# SensWear_Debug_UART2USB_1.net
KiCad netlist of a schematic drawn in Altium Designer
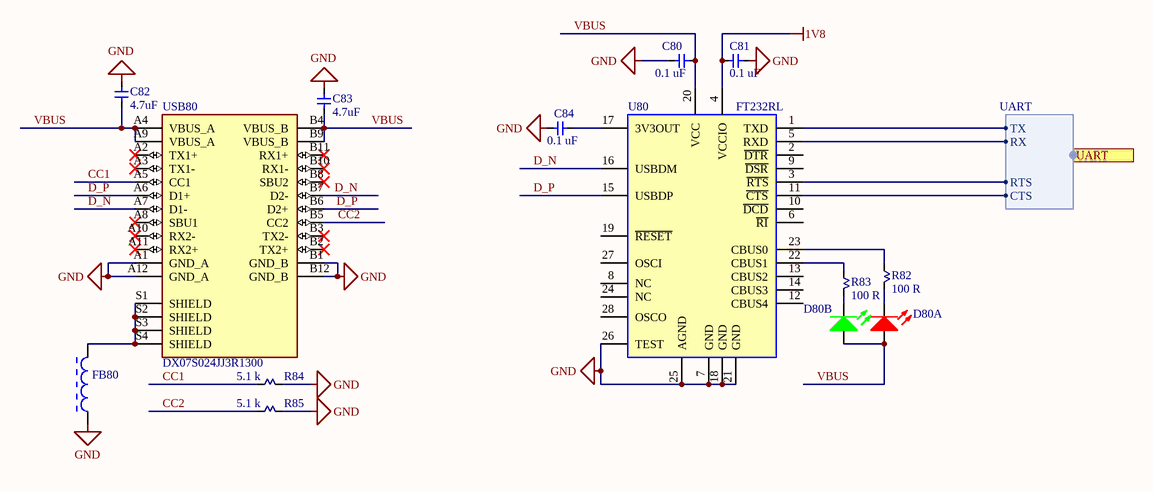
[diagram p0: SensWear_Debug_UART2USB_1.SchDoc]

(export (version "E")
  (design (tool "Eeschema 10.0.6"))
  (components
    (comp (ref "C80")
      (value "0.1 uF")
      (footprint "CAPC1005X05N")
      (description "CAP CER 0.1UF 16V X5R 0402")
      (fields
        (field (name "MANUFACTURER") "Murata Electronics")
        (field (name "MANUFACTURER PART NUMBER") "GRM155R61C104KA88D")
      )
      (libsource (lib "PingbitComponents") (part "GRM155R61C104KA88D"))
    )
    (comp (ref "C81")
      (value "0.1 uF")
      (footprint "CAPC1005X05N")
      (description "CAP CER 0.1UF 16V X5R 0402")
      (fields
        (field (name "MANUFACTURER") "Murata Electronics")
        (field (name "MANUFACTURER PART NUMBER") "GRM155R61C104KA88D")
      )
      (libsource (lib "PingbitComponents") (part "GRM155R61C104KA88D"))
    )
    (comp (ref "C82")
      (value "4.7uF")
      (footprint "CAPC1610X05N")
      (description "Cap Ceramic 4.7uF 10V X5R 10% Pad SMD 0603 85C T/R")
      (fields
        (field (name "MANUFACTURER") "Samsung")
        (field (name "MANUFACTURER PART NUMBER") "CL10A475KP8NNNC")
      )
      (libsource (lib "PingBitComponents") (part "CL10A475KP8NNNC"))
    )
    (comp (ref "C83")
      (value "4.7uF")
      (footprint "CAPC1610X05N")
      (description "Cap Ceramic 4.7uF 10V X5R 10% Pad SMD 0603 85C T/R")
      (fields
        (field (name "MANUFACTURER") "Samsung")
        (field (name "MANUFACTURER PART NUMBER") "CL10A475KP8NNNC")
      )
      (libsource (lib "PingBitComponents") (part "CL10A475KP8NNNC"))
    )
    (comp (ref "C84")
      (value "0.1 uF")
      (footprint "CAPC1005X05N")
      (description "CAP CER 0.1UF 16V X5R 0402")
      (fields
        (field (name "MANUFACTURER") "Murata Electronics")
        (field (name "MANUFACTURER PART NUMBER") "GRM155R61C104KA88D")
      )
      (libsource (lib "PingbitComponents") (part "GRM155R61C104KA88D"))
    )
    (comp (ref "D80")
      (value "LTST-C155KGJRKT")
      (footprint "LTST-C155KGJRKT")
      (description "LED GREEN/RED CLEAR CHIP SMD")
      (fields (field (name "MANUFACTURER") "Vishay Lite-On"))
      (libsource (lib "PingbitComponents") (part "LTST-C155KGJRKT"))
    )
    (comp (ref "FB80")
      (value "BLM15AG601SN1D")
      (footprint "MURA-BLM15-CHIP-2_V")
      (description "FERRITE BEAD 600 OHM 0402 1LN")
      (fields (field (name "MANUFACTURER") "Murata") (field (name "TOLERANCE") "25%"))
      (libsource (lib "PingBitComponents") (part "BLM15AG601SN1D"))
    )
    (comp (ref "R82")
      (value "100 R")
      (footprint "RESC1005X04N")
      (description "RES SMD 100 OHM 1% 1/10W 0402")
      (fields
        (field (name "MANUFACTURER") "Panasonic Electronic Components")
        (field (name "MANUFACTURER PART NUMBER") "ERJ-2RKF1000X")
      )
      (libsource (lib "PingBitComponents") (part "ERJ-2RKF1000X"))
    )
    (comp (ref "R83")
      (value "100 R")
      (footprint "RESC1005X04N")
      (description "RES SMD 100 OHM 1% 1/10W 0402")
      (fields
        (field (name "MANUFACTURER") "Panasonic Electronic Components")
        (field (name "MANUFACTURER PART NUMBER") "ERJ-2RKF1000X")
      )
      (libsource (lib "PingBitComponents") (part "ERJ-2RKF1000X"))
    )
    (comp (ref "R84")
      (value "5.1 k")
      (footprint "RESC1005X04N")
      (description "RES SMD 5.1K OHM 1% 1/10W 0402")
      (fields
        (field (name "MANUFACTURER") "Panasonic")
        (field (name "MANUFACTURER PART NUMBER") "ERJ-2RKF5101X")
      )
      (libsource (lib "PingbitComponents") (part "ERJ-2RKF5101X"))
    )
    (comp (ref "R85")
      (value "5.1 k")
      (footprint "RESC1005X04N")
      (description "RES SMD 5.1K OHM 1% 1/10W 0402")
      (fields
        (field (name "MANUFACTURER") "Panasonic")
        (field (name "MANUFACTURER PART NUMBER") "ERJ-2RKF5101X")
      )
      (libsource (lib "PingbitComponents") (part "ERJ-2RKF5101X"))
    )
    (comp (ref "U80")
      (value "FT232RL")
      (footprint "SOP65P780X200-28N")
      (description "IC USB FS SERIAL UART 28-SSOP")
      (fields
        (field (name "MANUFACTURER PART NUMBER") "FT232RL-REEL")
        (field (name "MANUFACTURER") "FTDI, Future Technology Devices International Ltd")
      )
      (libsource (lib "PingBitComponents") (part "FT232RL"))
    )
    (comp (ref "USB80")
      (value "DX07S024JJ3R1300")
      (footprint "JAE-DX07S024JJ3R1300-MFG")
      (description "Cut Tape - Usb Type C Receptacle Mid Mnt Dual R")
      (fields (field (name "MANUFACTURER") "JAE Electronics"))
      (libsource (lib "Connectors") (part "DX07S024JJ3R1300"))
    )
  )
  (nets
    (net (code "2") (name "/CC1") (class "Default")
      (node (ref "R84") (pin "1") (pinfunction "1_1") (pintype "passive"))
      (node (ref "USB80") (pin "A5") (pinfunction "CC1_A5") (pintype "bidirectional"))
    )
    (net (code "3") (name "/CC2") (class "Default")
      (node (ref "R85") (pin "1") (pinfunction "1_1") (pintype "passive"))
      (node (ref "USB80") (pin "B5") (pinfunction "CC2_B5") (pintype "bidirectional"))
    )
    (net (code "4") (name "/CTS") (class "Default")
      (node (ref "U80") (pin "11") (pinfunction "~{CTS}_11") (pintype "passive"))
    )
    (net (code "5") (name "/D_N") (class "Default")
      (node (ref "U80") (pin "16") (pinfunction "USBDM_16") (pintype "passive"))
      (node (ref "USB80") (pin "A7") (pinfunction "D1-_A7") (pintype "bidirectional"))
      (node (ref "USB80") (pin "B7") (pinfunction "D2-_B7") (pintype "bidirectional"))
    )
    (net (code "6") (name "/D_P") (class "Default")
      (node (ref "U80") (pin "15") (pinfunction "USBDP_15") (pintype "passive"))
      (node (ref "USB80") (pin "A6") (pinfunction "D1+_A6") (pintype "bidirectional"))
      (node (ref "USB80") (pin "B6") (pinfunction "D2+_B6") (pintype "bidirectional"))
    )
    (net (code "7") (name "/RTS") (class "Default")
      (node (ref "U80") (pin "3") (pinfunction "~{RTS}_3") (pintype "passive"))
    )
    (net (code "8") (name "/RX") (class "Default")
      (node (ref "U80") (pin "5") (pinfunction "RXD_5") (pintype "passive"))
    )
    (net (code "9") (name "/TX") (class "Default")
      (node (ref "U80") (pin "1") (pinfunction "TXD_1") (pintype "passive"))
    )
    (net (code "10") (name "/VBUS") (class "Default")
      (node (ref "C80") (pin "1") (pinfunction "1_1") (pintype "passive"))
      (node (ref "C82") (pin "2") (pinfunction "2_2") (pintype "passive"))
      (node (ref "C83") (pin "2") (pinfunction "2_2") (pintype "passive"))
      (node (ref "D80") (pin "1") (pinfunction "A_1") (pintype "passive"))
      (node (ref "D80") (pin "2") (pinfunction "A_2") (pintype "passive"))
      (node (ref "U80") (pin "20") (pinfunction "VCC_20") (pintype "passive"))
      (node (ref "USB80") (pin "A4") (pinfunction "VBUS_A_A4") (pintype "passive"))
      (node (ref "USB80") (pin "A9") (pinfunction "VBUS_A_A9") (pintype "passive"))
      (node (ref "USB80") (pin "B4") (pinfunction "VBUS_B_B4") (pintype "passive"))
      (node (ref "USB80") (pin "B9") (pinfunction "VBUS_B_B9") (pintype "passive"))
    )
    (net (code "12") (name "1V8") (class "Default")
      (node (ref "C81") (pin "2") (pinfunction "2_2") (pintype "passive"))
      (node (ref "U80") (pin "4") (pinfunction "VCCIO_4") (pintype "passive"))
    )
    (net (code "13") (name "GND") (class "Default")
      (node (ref "C80") (pin "2") (pinfunction "2_2") (pintype "passive"))
      (node (ref "C81") (pin "1") (pinfunction "1_1") (pintype "passive"))
      (node (ref "C82") (pin "1") (pinfunction "1_1") (pintype "passive"))
      (node (ref "C83") (pin "1") (pinfunction "1_1") (pintype "passive"))
      (node (ref "C84") (pin "2") (pinfunction "2_2") (pintype "passive"))
      (node (ref "FB80") (pin "1") (pinfunction "1_1") (pintype "passive"))
      (node (ref "R84") (pin "2") (pinfunction "2_2") (pintype "passive"))
      (node (ref "R85") (pin "2") (pinfunction "2_2") (pintype "passive"))
      (node (ref "U80") (pin "18") (pinfunction "GND_18") (pintype "passive"))
      (node (ref "U80") (pin "21") (pinfunction "GND_21") (pintype "passive"))
      (node (ref "U80") (pin "25") (pinfunction "AGND_25") (pintype "passive"))
      (node (ref "U80") (pin "26") (pinfunction "TEST_26") (pintype "passive"))
      (node (ref "U80") (pin "7") (pinfunction "GND_7") (pintype "passive"))
      (node (ref "USB80") (pin "A1") (pinfunction "GND_A_A1") (pintype "power_in"))
      (node (ref "USB80") (pin "A12") (pinfunction "GND_A_A12") (pintype "power_in"))
      (node (ref "USB80") (pin "B1") (pinfunction "GND_B_B1") (pintype "power_in"))
      (node (ref "USB80") (pin "B12") (pinfunction "GND_B_B12") (pintype "power_in"))
    )
    (net (code "14") (name "Net-(D80A-K)") (class "Default")
      (node (ref "D80") (pin "4") (pinfunction "K_4") (pintype "passive"))
      (node (ref "R82") (pin "1") (pinfunction "1_1") (pintype "passive"))
    )
    (net (code "15") (name "Net-(D80B-K)") (class "Default")
      (node (ref "D80") (pin "3") (pinfunction "K_3") (pintype "passive"))
      (node (ref "R83") (pin "1") (pinfunction "1_1") (pintype "passive"))
    )
    (net (code "16") (name "Net-(FB80-Pad2)") (class "Default")
      (node (ref "FB80") (pin "2") (pinfunction "2_2") (pintype "passive"))
      (node (ref "USB80") (pin "S1") (pinfunction "SHIELD_S1") (pintype "passive"))
      (node (ref "USB80") (pin "S2") (pinfunction "SHIELD_S2") (pintype "passive"))
      (node (ref "USB80") (pin "S3") (pinfunction "SHIELD_S3") (pintype "passive"))
      (node (ref "USB80") (pin "S4") (pinfunction "SHIELD_S4") (pintype "passive"))
    )
    (net (code "17") (name "Net-(U80-3V3OUT)") (class "Default")
      (node (ref "C84") (pin "1") (pinfunction "1_1") (pintype "passive"))
      (node (ref "U80") (pin "17") (pinfunction "3V3OUT_17") (pintype "passive"))
    )
    (net (code "18") (name "Net-(U80-CBUS0)") (class "Default")
      (node (ref "R82") (pin "2") (pinfunction "2_2") (pintype "passive"))
      (node (ref "U80") (pin "23") (pinfunction "CBUS0_23") (pintype "passive"))
    )
    (net (code "19") (name "Net-(U80-CBUS1)") (class "Default")
      (node (ref "R83") (pin "2") (pinfunction "2_2") (pintype "passive"))
      (node (ref "U80") (pin "22") (pinfunction "CBUS1_22") (pintype "passive"))
    )
    (net (code "20") (name "unconnected-(U80-CBUS2-Pad13)") (class "Default")
      (node (ref "U80") (pin "13") (pinfunction "CBUS2_13") (pintype "passive"))
    )
    (net (code "21") (name "unconnected-(U80-CBUS3-Pad14)") (class "Default")
      (node (ref "U80") (pin "14") (pinfunction "CBUS3_14") (pintype "passive"))
    )
    (net (code "22") (name "unconnected-(U80-CBUS4-Pad12)") (class "Default")
      (node (ref "U80") (pin "12") (pinfunction "CBUS4_12") (pintype "passive"))
    )
    (net (code "23") (name "unconnected-(U80-NC-Pad8)") (class "Default")
      (node (ref "U80") (pin "8") (pinfunction "NC_8") (pintype "passive"))
    )
    (net (code "24") (name "unconnected-(U80-NC-Pad24)") (class "Default")
      (node (ref "U80") (pin "24") (pinfunction "NC_24") (pintype "passive"))
    )
    (net (code "25") (name "unconnected-(U80-OSCI-Pad27)") (class "Default")
      (node (ref "U80") (pin "27") (pinfunction "OSCI_27") (pintype "passive"))
    )
    (net (code "26") (name "unconnected-(U80-OSCO-Pad28)") (class "Default")
      (node (ref "U80") (pin "28") (pinfunction "OSCO_28") (pintype "passive"))
    )
    (net (code "27") (name "unconnected-(U80-~{DCD}-Pad10)") (class "Default")
      (node (ref "U80") (pin "10") (pinfunction "~{DCD}_10") (pintype "passive"))
    )
    (net (code "28") (name "unconnected-(U80-~{DSR}-Pad9)") (class "Default")
      (node (ref "U80") (pin "9") (pinfunction "~{DSR}_9") (pintype "passive"))
    )
    (net (code "29") (name "unconnected-(U80-~{DTR}-Pad2)") (class "Default")
      (node (ref "U80") (pin "2") (pinfunction "~{DTR}_2") (pintype "passive"))
    )
    (net (code "30") (name "unconnected-(U80-~{RESET}-Pad19)") (class "Default")
      (node (ref "U80") (pin "19") (pinfunction "~{RESET}_19") (pintype "passive"))
    )
    (net (code "31") (name "unconnected-(U80-~{RI}-Pad6)") (class "Default")
      (node (ref "U80") (pin "6") (pinfunction "~{RI}_6") (pintype "passive"))
    )
    (net (code "32") (name "unconnected-(USB80-RX1+-PadB11)") (class "Default")
      (node (ref "USB80") (pin "B11") (pinfunction "RX1+_B11") (pintype "bidirectional+no_connect"))
    )
    (net (code "33") (name "unconnected-(USB80-RX1--PadB10)") (class "Default")
      (node (ref "USB80") (pin "B10") (pinfunction "RX1-_B10") (pintype "bidirectional+no_connect"))
    )
    (net (code "34") (name "unconnected-(USB80-RX2+-PadA11)") (class "Default")
      (node (ref "USB80") (pin "A11") (pinfunction "RX2+_A11") (pintype "bidirectional+no_connect"))
    )
    (net (code "35") (name "unconnected-(USB80-RX2--PadA10)") (class "Default")
      (node (ref "USB80") (pin "A10") (pinfunction "RX2-_A10") (pintype "bidirectional+no_connect"))
    )
    (net (code "36") (name "unconnected-(USB80-SBU1-PadA8)") (class "Default")
      (node (ref "USB80") (pin "A8") (pinfunction "SBU1_A8") (pintype "bidirectional+no_connect"))
    )
    (net (code "37") (name "unconnected-(USB80-SBU2-PadB8)") (class "Default")
      (node (ref "USB80") (pin "B8") (pinfunction "SBU2_B8") (pintype "bidirectional+no_connect"))
    )
    (net (code "38") (name "unconnected-(USB80-TX1+-PadA2)") (class "Default")
      (node (ref "USB80") (pin "A2") (pinfunction "TX1+_A2") (pintype "bidirectional+no_connect"))
    )
    (net (code "39") (name "unconnected-(USB80-TX1--PadA3)") (class "Default")
      (node (ref "USB80") (pin "A3") (pinfunction "TX1-_A3") (pintype "bidirectional+no_connect"))
    )
    (net (code "40") (name "unconnected-(USB80-TX2+-PadB2)") (class "Default")
      (node (ref "USB80") (pin "B2") (pinfunction "TX2+_B2") (pintype "bidirectional+no_connect"))
    )
    (net (code "41") (name "unconnected-(USB80-TX2--PadB3)") (class "Default")
      (node (ref "USB80") (pin "B3") (pinfunction "TX2-_B3") (pintype "bidirectional+no_connect"))
    )
  )
)
